# STM32.net
KiCad netlist of a schematic drawn in Altium Designer
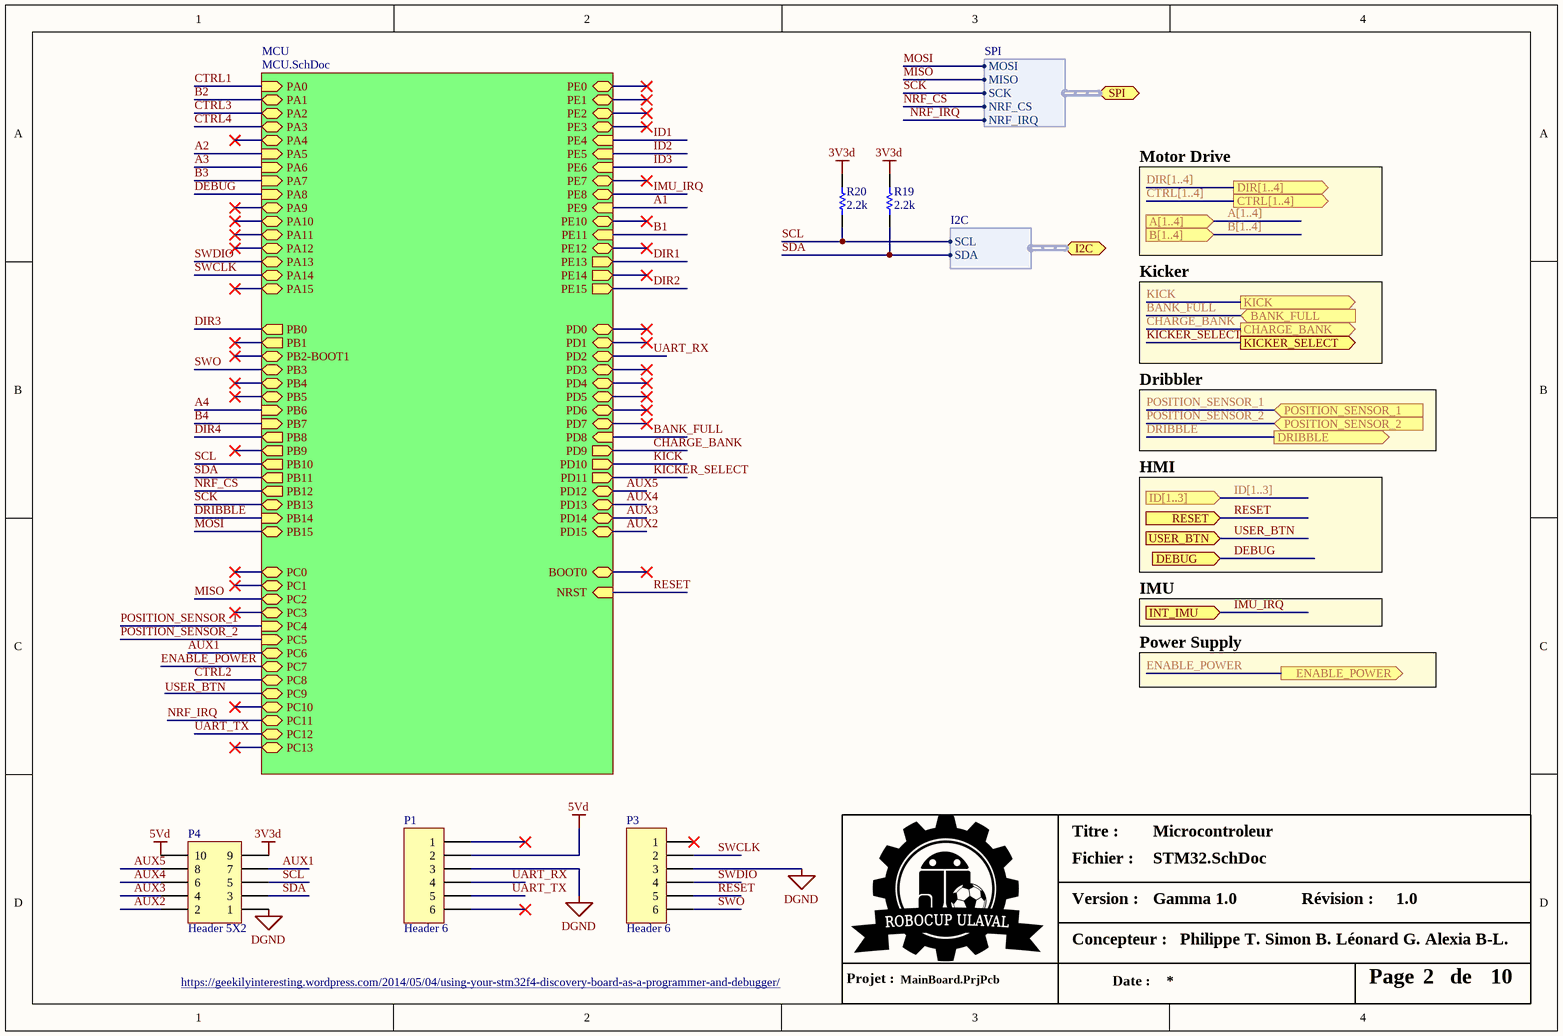
[diagram p0: STM32.SchDoc]

(export (version "E")
  (design (tool "Eeschema 10.0.6"))
  (components
    (comp (ref "P1")
      (value "Header 6")
      (footprint "HDR1X6")
      (description "Header, 6-Pin")
      (fields (field (name "PUBLISHER") "Altium Limited"))
      (libsource (lib "Miscellaneous Connectors") (part "Header 6"))
    )
    (comp (ref "P3")
      (value "Header 6")
      (footprint "HDR1X6")
      (description "Header, 6-Pin")
      (fields (field (name "PUBLISHER") "Altium Limited"))
      (libsource (lib "Miscellaneous Connectors") (part "Header 6"))
    )
    (comp (ref "P4")
      (value "Header 5X2")
      (footprint "HDR2X5")
      (description "Header, 5-Pin, Dual row")
      (fields (field (name "PUBLISHER") "Altium Limited"))
      (libsource (lib "Miscellaneous Connectors") (part "Header 5X2"))
    )
    (comp (ref "R19")
      (value "RC0603FR-072K2L")
      (footprint "0603")
      (description "RES SMD 2.2K OHM 1% 1/10W 0603")
      (fields
        (field (name "MANUFACTURER") "Yageo")
        (field (name "TOLERANCE") "±1%")
        (field (name "RESISTANCE (OHMS)") "2.2k")
      )
      (libsource (lib "ResCap") (part "RC0603FR-072K2L"))
    )
    (comp (ref "R20")
      (value "RC0603FR-072K2L")
      (footprint "0603")
      (description "RES SMD 2.2K OHM 1% 1/10W 0603")
      (fields
        (field (name "MANUFACTURER") "Yageo")
        (field (name "TOLERANCE") "±1%")
        (field (name "RESISTANCE (OHMS)") "2.2k")
      )
      (libsource (lib "ResCap") (part "RC0603FR-072K2L"))
    )
  )
  (nets
    (net (code "7") (name "/AUX1") (class "Default")
      (node (ref "P4") (pin "7") (pinfunction "7_7") (pintype "passive"))
    )
    (net (code "8") (name "/AUX2") (class "Default")
      (node (ref "P4") (pin "2") (pinfunction "2_2") (pintype "passive"))
    )
    (net (code "9") (name "/AUX3") (class "Default")
      (node (ref "P4") (pin "4") (pinfunction "4_4") (pintype "passive"))
    )
    (net (code "10") (name "/AUX4") (class "Default")
      (node (ref "P4") (pin "6") (pinfunction "6_6") (pintype "passive"))
    )
    (net (code "11") (name "/AUX5") (class "Default")
      (node (ref "P4") (pin "8") (pinfunction "8_8") (pintype "passive"))
    )
    (net (code "79") (name "/RESET") (class "Default")
      (node (ref "P3") (pin "5") (pinfunction "5_5") (pintype "passive"))
    )
    (net (code "81") (name "/SCL") (class "Default")
      (node (ref "P4") (pin "5") (pinfunction "5_5") (pintype "passive"))
      (node (ref "R20") (pin "1") (pinfunction "1_1") (pintype "passive"))
    )
    (net (code "82") (name "/SDA") (class "Default")
      (node (ref "P4") (pin "3") (pinfunction "3_3") (pintype "passive"))
      (node (ref "R19") (pin "1") (pinfunction "1_1") (pintype "passive"))
    )
    (net (code "83") (name "/SWCLK") (class "Default")
      (node (ref "P3") (pin "2") (pinfunction "2_2") (pintype "passive"))
    )
    (net (code "84") (name "/SWDIO") (class "Default")
      (node (ref "P3") (pin "4") (pinfunction "4_4") (pintype "passive"))
    )
    (net (code "85") (name "/SWO") (class "Default")
      (node (ref "P3") (pin "6") (pinfunction "6_6") (pintype "passive"))
    )
    (net (code "86") (name "/UART_RX") (class "Default")
      (node (ref "P1") (pin "4") (pinfunction "4_4") (pintype "passive"))
    )
    (net (code "87") (name "/UART_TX") (class "Default")
      (node (ref "P1") (pin "5") (pinfunction "5_5") (pintype "passive"))
    )
    (net (code "91") (name "3V3d") (class "Default")
      (node (ref "P4") (pin "9") (pinfunction "9_9") (pintype "passive"))
      (node (ref "R19") (pin "2") (pinfunction "2_2") (pintype "passive"))
      (node (ref "R20") (pin "2") (pinfunction "2_2") (pintype "passive"))
    )
    (net (code "92") (name "5Vd") (class "Default")
      (node (ref "P1") (pin "2") (pinfunction "2_2") (pintype "passive"))
      (node (ref "P4") (pin "10") (pinfunction "10_10") (pintype "passive"))
    )
    (net (code "93") (name "DGND") (class "Default")
      (node (ref "P1") (pin "3") (pinfunction "3_3") (pintype "passive"))
      (node (ref "P3") (pin "3") (pinfunction "3_3") (pintype "passive"))
      (node (ref "P4") (pin "1") (pinfunction "1_1") (pintype "passive"))
    )
    (net (code "94") (name "unconnected-(P1-Pad1)") (class "Default")
      (node (ref "P1") (pin "1") (pinfunction "1_1") (pintype "passive+no_connect"))
    )
    (net (code "95") (name "unconnected-(P1-Pad6)") (class "Default")
      (node (ref "P1") (pin "6") (pinfunction "6_6") (pintype "passive+no_connect"))
    )
    (net (code "96") (name "unconnected-(P3-Pad1)") (class "Default")
      (node (ref "P3") (pin "1") (pinfunction "1_1") (pintype "passive+no_connect"))
    )
  )
)
